# Sheet1.net
KiCad netlist of a schematic drawn in Altium Designer
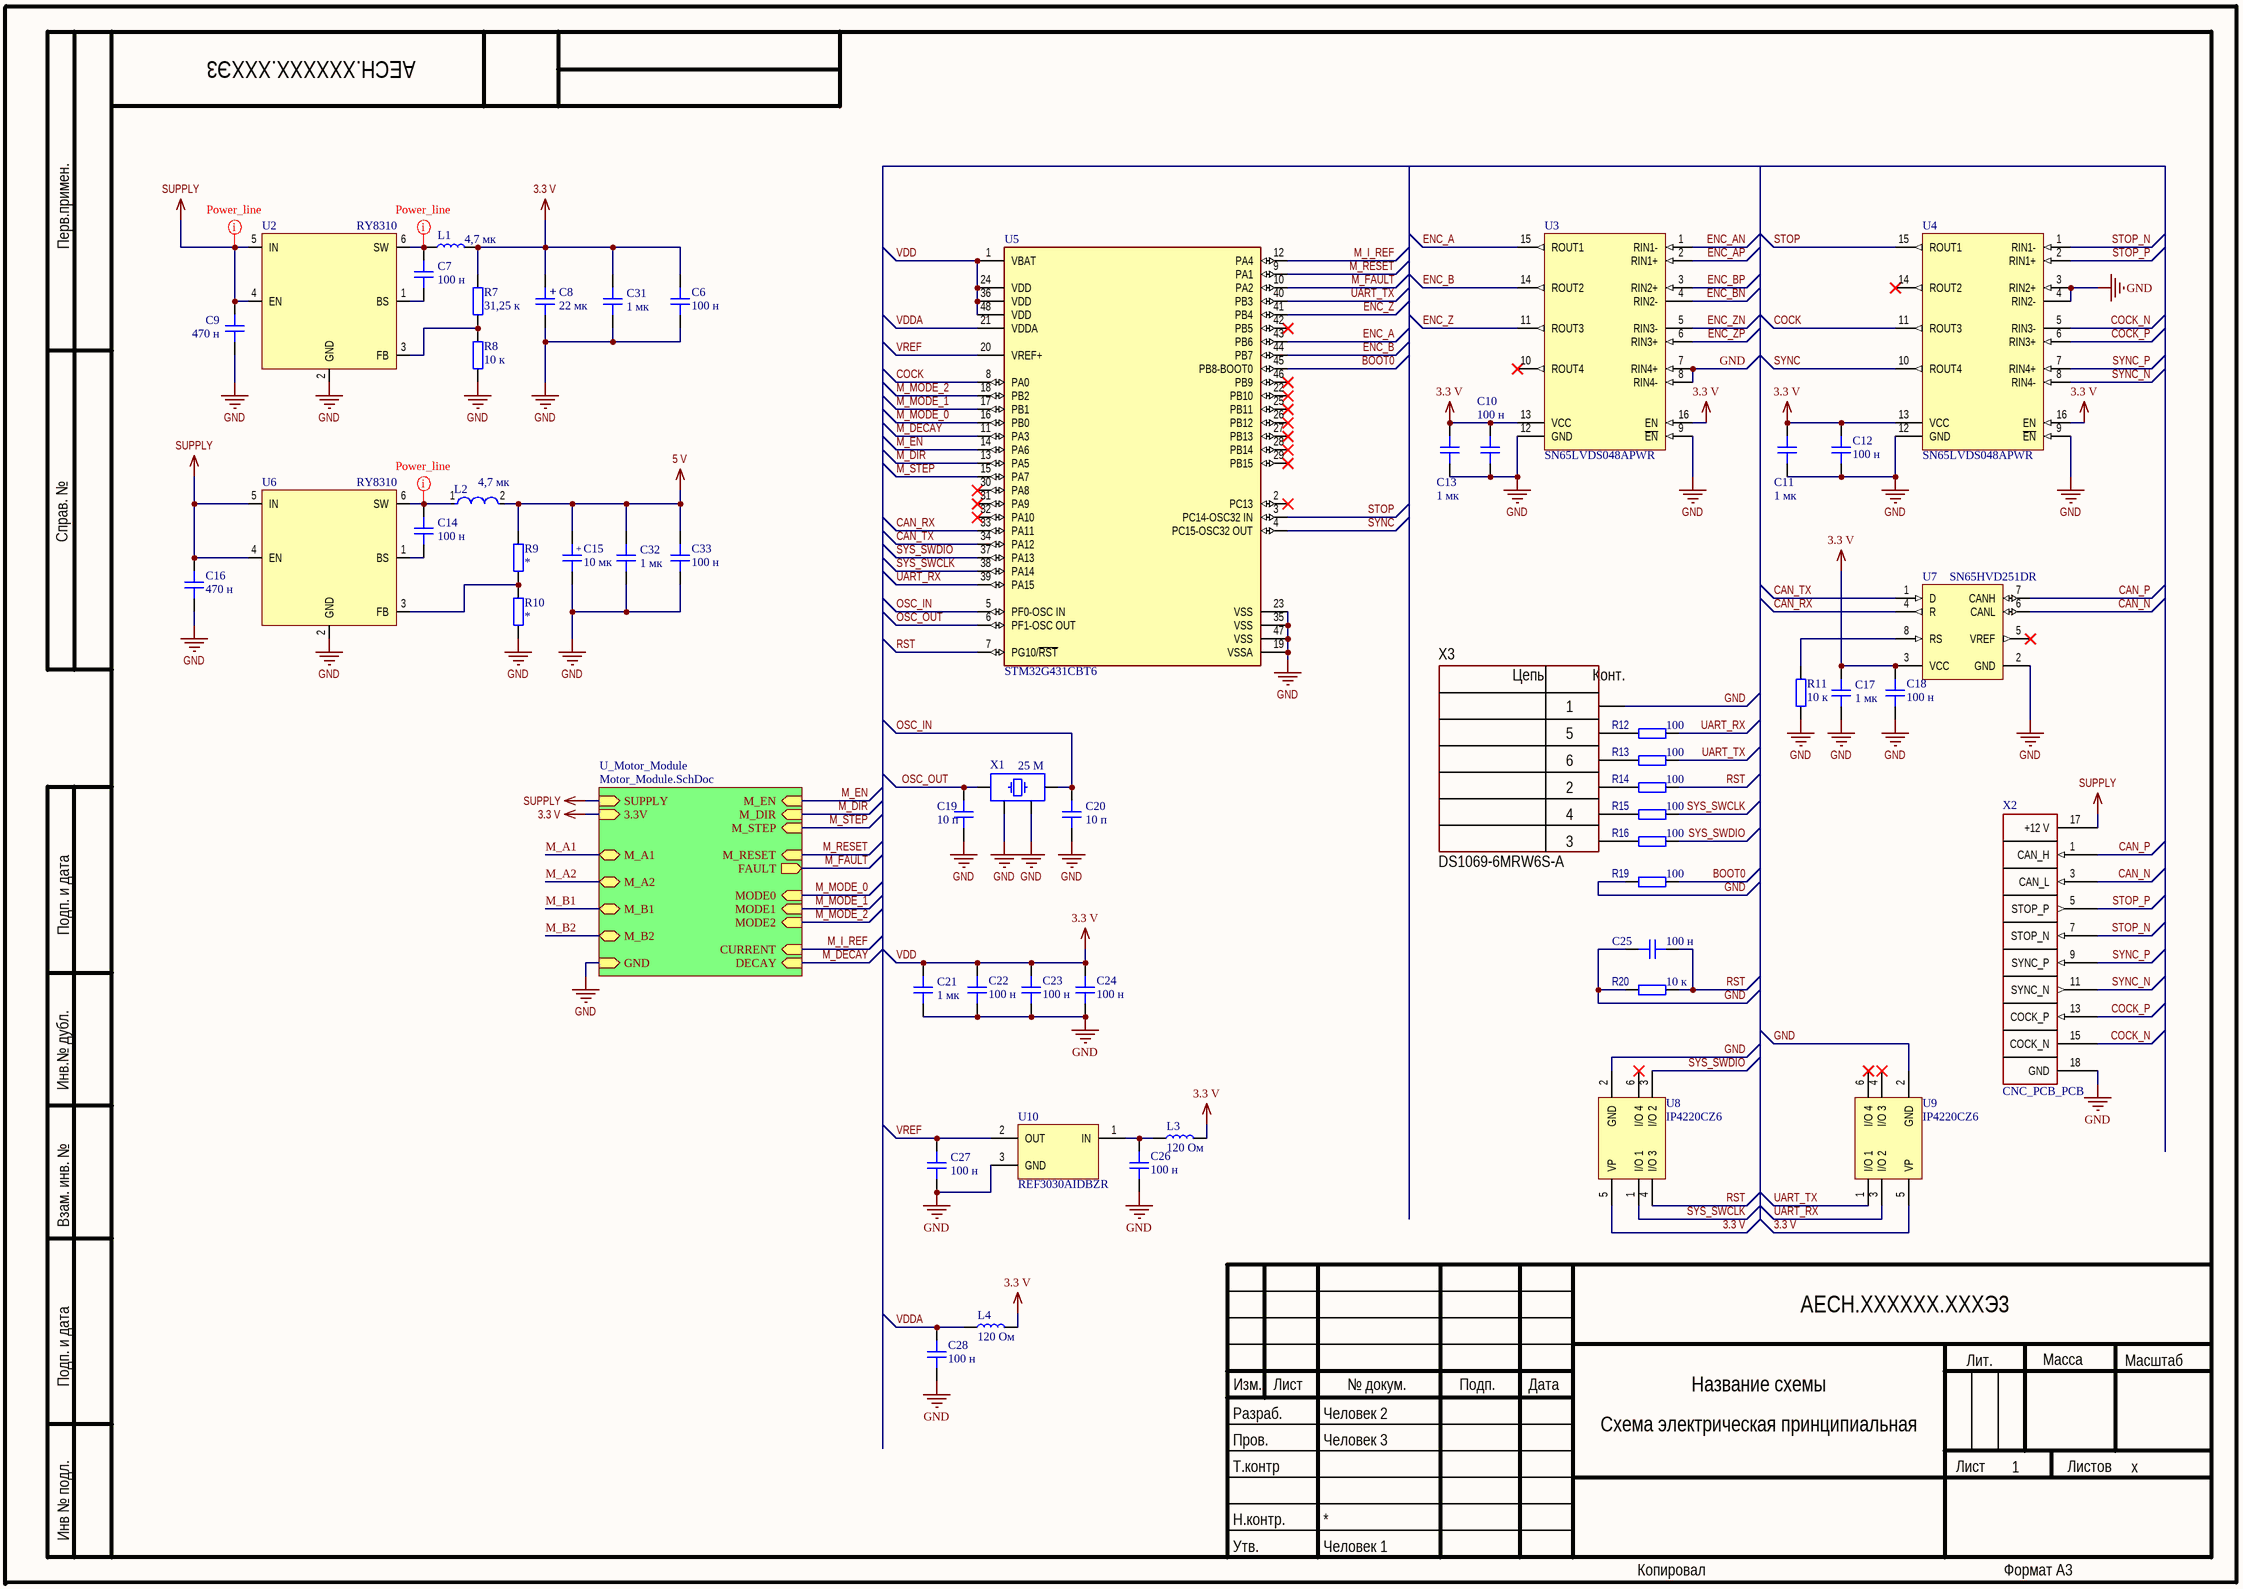
[diagram p0: Sheet1.SchDoc]

(export (version "E")
  (design (tool "Eeschema 10.0.6"))
  (components
    (comp (ref "C6")
      (value "100 н")
      (footprint "CAP_0603")
      (description "Керамический конденсатор")
      (libsource (lib "Schematic-Lib-PhilsLab") (part "CAP_0603"))
    )
    (comp (ref "C7")
      (value "100 н")
      (footprint "CAP_0603")
      (description "Керамический конденсатор")
      (libsource (lib "Schematic-Lib-PhilsLab") (part "CAP_0805"))
    )
    (comp (ref "C8")
      (value "22 мк")
      (footprint "TANTAL_B")
      (description "Танталовый конденсатор")
      (fields (field (name "VOLTAGE") "6,3"))
      (libsource (lib "Schematic-Lib-PhilsLab") (part "CAP_ALEL_16x16.5_25V"))
    )
    (comp (ref "C9")
      (value "470 н")
      (footprint "CAP_0805")
      (description "Capacitor SMD 0805")
      (fields (field (name "VOLTAGE") "50"))
      (libsource (lib "Schematic-Lib-PhilsLab") (part "CAP_0805"))
    )
    (comp (ref "C10")
      (value "100 н")
      (footprint "CAP_0603")
      (description "Керамический конденсатор")
      (libsource (lib "Schematic-Lib-PhilsLab") (part "CAP_0603"))
    )
    (comp (ref "C11")
      (value "1 мк")
      (footprint "CAP_0603")
      (description "Керамический конденсатор")
      (libsource (lib "Schematic-Lib-PhilsLab") (part "CAP_0603"))
    )
    (comp (ref "C12")
      (value "100 н")
      (footprint "CAP_0603")
      (description "Керамический конденсатор")
      (libsource (lib "Schematic-Lib-PhilsLab") (part "CAP_0603"))
    )
    (comp (ref "C13")
      (value "1 мк")
      (footprint "CAP_0603")
      (description "Керамический конденсатор")
      (libsource (lib "Schematic-Lib-PhilsLab") (part "CAP_0603"))
    )
    (comp (ref "C14")
      (value "100 н")
      (footprint "CAP_0603")
      (description "Керамический конденсатор")
      (libsource (lib "Schematic-Lib-PhilsLab") (part "CAP_0805"))
    )
    (comp (ref "C15")
      (value "10 мк")
      (footprint "CAP_TANT_0603")
      (description "Capacitor SMD Tantalum 0603")
      (fields (field (name "VOLTAGE") "6,3"))
      (libsource (lib "Schematic-Lib-PhilsLab") (part "CAP_TANT_0603"))
    )
    (comp (ref "C16")
      (value "470 н")
      (footprint "CAP_0805")
      (description "Capacitor SMD 0805")
      (fields (field (name "VOLTAGE") "50"))
      (libsource (lib "Schematic-Lib-PhilsLab") (part "CAP_0805"))
    )
    (comp (ref "C17")
      (value "1 мк")
      (footprint "CAP_0603")
      (description "Керамический конденсатор")
      (libsource (lib "Schematic-Lib-PhilsLab") (part "CAP_0603"))
    )
    (comp (ref "C18")
      (value "100 н")
      (footprint "CAP_0603")
      (description "Керамический конденсатор")
      (libsource (lib "Schematic-Lib-PhilsLab") (part "CAP_0603"))
    )
    (comp (ref "C19")
      (value "10 п")
      (footprint "CAP_0603")
      (description "Керамический конденсатор")
      (libsource (lib "Schematic-Lib-PhilsLab") (part "CAP_0603"))
    )
    (comp (ref "C20")
      (value "10 п")
      (footprint "CAP_0603")
      (description "Керамический конденсатор")
      (libsource (lib "Schematic-Lib-PhilsLab") (part "CAP_0603"))
    )
    (comp (ref "C21")
      (value "1 мк")
      (footprint "CAP_0603")
      (description "Керамический конденсатор")
      (libsource (lib "Schematic-Lib-PhilsLab") (part "CAP_0603"))
    )
    (comp (ref "C22")
      (value "100 н")
      (footprint "CAP_0603")
      (description "Керамический конденсатор")
      (libsource (lib "Schematic-Lib-PhilsLab") (part "CAP_0603"))
    )
    (comp (ref "C23")
      (value "100 н")
      (footprint "CAP_0603")
      (description "Керамический конденсатор")
      (libsource (lib "Schematic-Lib-PhilsLab") (part "CAP_0603"))
    )
    (comp (ref "C24")
      (value "100 н")
      (footprint "CAP_0603")
      (description "Керамический конденсатор")
      (libsource (lib "Schematic-Lib-PhilsLab") (part "CAP_0603"))
    )
    (comp (ref "C25")
      (value "100 н")
      (footprint "CAP_0603")
      (description "Керамический конденсатор")
      (libsource (lib "Schematic-Lib-PhilsLab") (part "CAP_0603"))
    )
    (comp (ref "C26")
      (value "100 н")
      (footprint "CAP_0603")
      (description "Capacitor SMD 0603")
      (libsource (lib "Schematic-Lib-PhilsLab") (part "CAP_0603"))
    )
    (comp (ref "C27")
      (value "100 н")
      (footprint "CAP_0603")
      (description "Керамический конденсатор")
      (libsource (lib "Schematic-Lib-PhilsLab") (part "CAP_0603"))
    )
    (comp (ref "C28")
      (value "100 н")
      (footprint "CAP_0603")
      (description "Capacitor SMD 0603")
      (libsource (lib "Schematic-Lib-PhilsLab") (part "CAP_0603"))
    )
    (comp (ref "C31")
      (value "1 мк")
      (footprint "CAP_0603")
      (description "Керамический конденсатор")
      (libsource (lib "Schematic-Lib-PhilsLab") (part "CAP_0603"))
    )
    (comp (ref "C32")
      (value "1 мк")
      (footprint "CAP_0603")
      (description "Керамический конденсатор")
      (libsource (lib "Schematic-Lib-PhilsLab") (part "CAP_0603"))
    )
    (comp (ref "C33")
      (value "100 н")
      (footprint "CAP_0603")
      (description "Керамический конденсатор")
      (libsource (lib "Schematic-Lib-PhilsLab") (part "CAP_0603"))
    )
    (comp (ref "L1")
      (value "4,7 мк")
      (footprint "IND_1008")
      (description "Inductor SMD 1008")
      (libsource (lib "Schematic-Lib-PhilsLab") (part "IND_1008"))
    )
    (comp (ref "L2")
      (value "4,7 мк")
      (footprint "FP-LQM21PH_G0-IPC_C")
      (description "Multilayer Type Inductor for Power Lines, 0805 (2012), 4.7μH, 20%, 0.288Ω, 0.8A")
      (libsource (lib "Altium Content Vault") (part "725321dda6339637d4d059423bc1c3c"))
    )
    (comp (ref "L3")
      (value "120 Ом")
      (footprint "IND_0603")
      (description "Inductor SMD 0603")
      (libsource (lib "Schematic-Lib-PhilsLab") (part "IND_0603"))
    )
    (comp (ref "L4")
      (value "120 Ом")
      (footprint "IND_0603")
      (description "Inductor SMD 0603")
      (libsource (lib "Schematic-Lib-PhilsLab") (part "IND_0603"))
    )
    (comp (ref "R7")
      (value "31,25 к")
      (footprint "RES_0603")
      (description "Резистор")
      (libsource (lib "Schematic-Lib-PhilsLab") (part "RES_0805"))
    )
    (comp (ref "R8")
      (value "10 к")
      (footprint "RES_0603")
      (description "Резистор")
      (libsource (lib "Schematic-Lib-PhilsLab") (part "RES_0805"))
    )
    (comp (ref "R9")
      (value "*")
      (footprint "RES_0603")
      (description "Резистор")
      (libsource (lib "Schematic-Lib-PhilsLab") (part "RES_0805"))
    )
    (comp (ref "R10")
      (value "*")
      (footprint "RES_0603")
      (description "Резистор")
      (libsource (lib "Schematic-Lib-PhilsLab") (part "RES_0805"))
    )
    (comp (ref "R11")
      (value "10 к")
      (footprint "RES_0603")
      (description "Резистор")
      (libsource (lib "Schematic-Lib-PhilsLab") (part "RES_0603"))
    )
    (comp (ref "R12")
      (value "100")
      (footprint "RES_0603")
      (description "Резистор")
      (libsource (lib "Schematic-Lib-PhilsLab") (part "RES_0603"))
    )
    (comp (ref "R13")
      (value "100")
      (footprint "RES_0603")
      (description "Резистор")
      (libsource (lib "Schematic-Lib-PhilsLab") (part "RES_0603"))
    )
    (comp (ref "R14")
      (value "100")
      (footprint "RES_0603")
      (description "Резистор")
      (libsource (lib "Schematic-Lib-PhilsLab") (part "RES_0603"))
    )
    (comp (ref "R15")
      (value "100")
      (footprint "RES_0603")
      (description "Резистор")
      (libsource (lib "Schematic-Lib-PhilsLab") (part "RES_0603"))
    )
    (comp (ref "R16")
      (value "100")
      (footprint "RES_0603")
      (description "Резистор")
      (libsource (lib "Schematic-Lib-PhilsLab") (part "RES_0603"))
    )
    (comp (ref "R19")
      (value "100")
      (footprint "RES_0603")
      (description "Резистор")
      (libsource (lib "Schematic-Lib-PhilsLab") (part "RES_0603"))
    )
    (comp (ref "R20")
      (value "10 к")
      (footprint "RES_0603")
      (description "Резистор")
      (libsource (lib "Schematic-Lib-PhilsLab") (part "RES_0603"))
    )
    (comp (ref "U2")
      (value "RY8310")
      (footprint "SOT-23-6")
      (description "Понижающий DC-DC")
      (libsource (lib "Schematic-Lib-PhilsLab") (part "MT2492"))
    )
    (comp (ref "U3")
      (value "SN65LVDS048APWR")
      (footprint "MTC16_M")
      (description "Драйвер LVDS")
      (libsource (lib "Altium Content Vault") (part "IN-LNDRV-DS90LV047ATM"))
    )
    (comp (ref "U4")
      (value "SN65LVDS048APWR")
      (footprint "MTC16_M")
      (description "Драйвер LVDS")
      (libsource (lib "Altium Content Vault") (part "IN-LNDRV-DS90LV047ATM"))
    )
    (comp (ref "U5")
      (value "STM32G431CBT6")
      (footprint "FP-LQFP48-5B-MFG")
      (description "MAINSTREAM ARM CORTEX-M4+ MCU 17")
      (libsource (lib "Altium Content Vault") (part "08b09c1d51ec08ade740842f2b8671b"))
    )
    (comp (ref "U6")
      (value "RY8310")
      (footprint "SOT-23-6")
      (description "Понижающий DC-DC")
      (libsource (lib "Schematic-Lib-PhilsLab") (part "MT2492"))
    )
    (comp (ref "U7")
      (value "SN65HVD251DR")
      (footprint "D0008A_N")
      (description "Драйвер CAN")
      (libsource (lib "Altium Content Vault") (part "TI-SN65HVD251-SOIC_D-8"))
    )
    (comp (ref "U8")
      (value "IP4220CZ6")
      (footprint "NXP-SOT457_L")
      (description "Сборка защитных диодов")
      (libsource (lib "") (part "NXP-IP4220CZ6-6_1"))
    )
    (comp (ref "U9")
      (value "IP4220CZ6")
      (footprint "NXP-SOT457_L")
      (description "Сборка защитных диодов")
      (libsource (lib "Altium Content Vault") (part "NXP-IP4220CZ6-6"))
    )
    (comp (ref "U10")
      (value "REF3030AIDBZR")
      (footprint "DBZ0003A_N")
      (libsource (lib "Altium Content Vault") (part "TI-REF3020DBZ3"))
    )
    (comp (ref "X1")
      (value "25 M")
      (footprint "XTAL_3225")
      (description "Кварцевый резонатор")
      (libsource (lib "Schematic-Lib-PhilsLab") (part "TSX-3225_24.0000MF15X-AC"))
    )
    (comp (ref "X2")
      (value "CNC_PCB_PCB")
      (footprint "CNC_PCB_PCB")
      (libsource (lib "BarkockLib") (part "CNC_PCB_PCB"))
    )
    (comp (ref "X3")
      (value "DS1069-6MRW6S-A")
      (footprint "CON: CWF-6R")
      (libsource (lib "Connectors") (part "6-Connector"))
    )
  )
  (nets
    (net (code "1") (name "/BOOT0") (class "Default")
      (node (ref "R19") (pin "1") (pinfunction "1_1") (pintype "passive"))
      (node (ref "U5") (pin "45") (pinfunction "PB8-BOOT0_45") (pintype "bidirectional"))
    )
    (net (code "2") (name "/CAN_N") (class "Default")
      (node (ref "U7") (pin "6") (pinfunction "CANL_6") (pintype "bidirectional"))
      (node (ref "X2") (pin "3") (pinfunction "CAN_L_3") (pintype "input"))
    )
    (net (code "3") (name "/CAN_P") (class "Default")
      (node (ref "U7") (pin "7") (pinfunction "CANH_7") (pintype "bidirectional"))
      (node (ref "X2") (pin "1") (pinfunction "CAN_H_1") (pintype "input"))
    )
    (net (code "4") (name "/CAN_RX") (class "Default")
      (node (ref "U5") (pin "33") (pinfunction "PA11_33") (pintype "bidirectional"))
      (node (ref "U7") (pin "4") (pinfunction "R_4") (pintype "output"))
    )
    (net (code "5") (name "/CAN_TX") (class "Default")
      (node (ref "U5") (pin "34") (pinfunction "PA12_34") (pintype "bidirectional"))
      (node (ref "U7") (pin "1") (pinfunction "D_1") (pintype "input"))
    )
    (net (code "6") (name "/COCK") (class "Default")
      (node (ref "U4") (pin "11") (pinfunction "ROUT3_11") (pintype "output"))
      (node (ref "U5") (pin "8") (pinfunction "PA0_8") (pintype "bidirectional"))
    )
    (net (code "7") (name "/COCK_N") (class "Default")
      (node (ref "U4") (pin "5") (pinfunction "RIN3-_5") (pintype "power_in"))
      (node (ref "X2") (pin "15") (pinfunction "COCK_N_15") (pintype "power_in"))
    )
    (net (code "8") (name "/COCK_P") (class "Default")
      (node (ref "U4") (pin "6") (pinfunction "RIN3+_6") (pintype "input"))
      (node (ref "X2") (pin "13") (pinfunction "COCK_P_13") (pintype "input"))
    )
    (net (code "9") (name "/ENC_A") (class "Default")
      (node (ref "U3") (pin "15") (pinfunction "ROUT1_15") (pintype "output"))
      (node (ref "U5") (pin "43") (pinfunction "PB6_43") (pintype "bidirectional"))
    )
    (net (code "10") (name "/ENC_AN") (class "Default")
      (node (ref "U3") (pin "1") (pinfunction "RIN1-_1") (pintype "input"))
    )
    (net (code "11") (name "/ENC_AP") (class "Default")
      (node (ref "U3") (pin "2") (pinfunction "RIN1+_2") (pintype "input"))
    )
    (net (code "12") (name "/ENC_B") (class "Default")
      (node (ref "U3") (pin "14") (pinfunction "ROUT2_14") (pintype "output"))
      (node (ref "U5") (pin "44") (pinfunction "PB7_44") (pintype "bidirectional"))
    )
    (net (code "13") (name "/ENC_BN") (class "Default")
      (node (ref "U3") (pin "4") (pinfunction "RIN2-_4") (pintype "power_in"))
    )
    (net (code "14") (name "/ENC_BP") (class "Default")
      (node (ref "U3") (pin "3") (pinfunction "RIN2+_3") (pintype "input"))
    )
    (net (code "15") (name "/ENC_Z") (class "Default")
      (node (ref "U3") (pin "11") (pinfunction "ROUT3_11") (pintype "output"))
      (node (ref "U5") (pin "41") (pinfunction "PB4_41") (pintype "bidirectional"))
    )
    (net (code "16") (name "/ENC_ZN") (class "Default")
      (node (ref "U3") (pin "5") (pinfunction "RIN3-_5") (pintype "power_in"))
    )
    (net (code "17") (name "/ENC_ZP") (class "Default")
      (node (ref "U3") (pin "6") (pinfunction "RIN3+_6") (pintype "input"))
    )
    (net (code "22") (name "/M_DECAY") (class "Default")
      (node (ref "U5") (pin "11") (pinfunction "PA3_11") (pintype "bidirectional"))
    )
    (net (code "23") (name "/M_DIR") (class "Default")
      (node (ref "U5") (pin "13") (pinfunction "PA5_13") (pintype "bidirectional"))
    )
    (net (code "24") (name "/M_EN") (class "Default")
      (node (ref "U5") (pin "14") (pinfunction "PA6_14") (pintype "bidirectional"))
    )
    (net (code "25") (name "/M_FAULT") (class "Default")
      (node (ref "U5") (pin "10") (pinfunction "PA2_10") (pintype "bidirectional"))
    )
    (net (code "26") (name "/M_I_REF") (class "Default")
      (node (ref "U5") (pin "12") (pinfunction "PA4_12") (pintype "bidirectional"))
    )
    (net (code "27") (name "/M_MODE_0") (class "Default")
      (node (ref "U5") (pin "16") (pinfunction "PB0_16") (pintype "bidirectional"))
    )
    (net (code "28") (name "/M_MODE_1") (class "Default")
      (node (ref "U5") (pin "17") (pinfunction "PB1_17") (pintype "bidirectional"))
    )
    (net (code "29") (name "/M_MODE_2") (class "Default")
      (node (ref "U5") (pin "18") (pinfunction "PB2_18") (pintype "bidirectional"))
    )
    (net (code "30") (name "/M_RESET") (class "Default")
      (node (ref "U5") (pin "9") (pinfunction "PA1_9") (pintype "bidirectional"))
    )
    (net (code "31") (name "/M_STEP") (class "Default")
      (node (ref "U5") (pin "15") (pinfunction "PA7_15") (pintype "bidirectional"))
    )
    (net (code "32") (name "/OSC_IN") (class "Default")
      (node (ref "C20") (pin "1") (pinfunction "1_1") (pintype "passive"))
      (node (ref "U5") (pin "5") (pinfunction "PF0-OSC_IN_5") (pintype "bidirectional"))
      (node (ref "X1") (pin "3") (pinfunction "3_3") (pintype "passive"))
    )
    (net (code "33") (name "/OSC_OUT") (class "Default")
      (node (ref "C19") (pin "1") (pinfunction "1_1") (pintype "passive"))
      (node (ref "U5") (pin "6") (pinfunction "PF1-OSC_OUT_6") (pintype "bidirectional"))
      (node (ref "X1") (pin "1") (pinfunction "1_1") (pintype "passive"))
    )
    (net (code "34") (name "/RST") (class "Default")
      (node (ref "C25") (pin "2") (pinfunction "2_2") (pintype "passive"))
      (node (ref "R14") (pin "1") (pinfunction "1_1") (pintype "passive"))
      (node (ref "R20") (pin "1") (pinfunction "1_1") (pintype "passive"))
      (node (ref "U5") (pin "7") (pinfunction "PG10/~{RST}_7") (pintype "bidirectional"))
      (node (ref "U8") (pin "4") (pinfunction "I/O_3_4") (pintype "passive"))
    )
    (net (code "35") (name "/STOP") (class "Default")
      (node (ref "U4") (pin "15") (pinfunction "ROUT1_15") (pintype "output"))
      (node (ref "U5") (pin "3") (pinfunction "PC14-OSC32_IN_3") (pintype "bidirectional"))
    )
    (net (code "36") (name "/STOP_N") (class "Default")
      (node (ref "U4") (pin "1") (pinfunction "RIN1-_1") (pintype "input"))
      (node (ref "X2") (pin "7") (pinfunction "STOP_N_7") (pintype "input"))
    )
    (net (code "37") (name "/STOP_P") (class "Default")
      (node (ref "U4") (pin "2") (pinfunction "RIN1+_2") (pintype "input"))
      (node (ref "X2") (pin "5") (pinfunction "STOP_P_5") (pintype "output"))
    )
    (net (code "38") (name "/SYNC") (class "Default")
      (node (ref "U4") (pin "10") (pinfunction "ROUT4_10") (pintype "output"))
      (node (ref "U5") (pin "4") (pinfunction "PC15-OSC32_OUT_4") (pintype "bidirectional"))
    )
    (net (code "39") (name "/SYNC_N") (class "Default")
      (node (ref "U4") (pin "8") (pinfunction "RIN4-_8") (pintype "input"))
      (node (ref "X2") (pin "11") (pinfunction "SYNC_N_11") (pintype "output"))
    )
    (net (code "40") (name "/SYNC_P") (class "Default")
      (node (ref "U4") (pin "7") (pinfunction "RIN4+_7") (pintype "input"))
      (node (ref "X2") (pin "9") (pinfunction "SYNC_P_9") (pintype "input"))
    )
    (net (code "41") (name "/SYS_SWCLK") (class "Default")
      (node (ref "R15") (pin "1") (pinfunction "1_1") (pintype "passive"))
      (node (ref "U5") (pin "38") (pinfunction "PA14_38") (pintype "bidirectional"))
      (node (ref "U8") (pin "1") (pinfunction "I/O_1_1") (pintype "passive"))
    )
    (net (code "42") (name "/SYS_SWDIO") (class "Default")
      (node (ref "R16") (pin "1") (pinfunction "1_1") (pintype "passive"))
      (node (ref "U5") (pin "37") (pinfunction "PA13_37") (pintype "bidirectional"))
      (node (ref "U8") (pin "3") (pinfunction "I/O_2_3") (pintype "passive"))
    )
    (net (code "43") (name "/UART_RX") (class "Default")
      (node (ref "R12") (pin "1") (pinfunction "1_1") (pintype "passive"))
      (node (ref "U5") (pin "39") (pinfunction "PA15_39") (pintype "bidirectional"))
      (node (ref "U9") (pin "3") (pinfunction "I/O_2_3") (pintype "passive"))
    )
    (net (code "44") (name "/UART_TX") (class "Default")
      (node (ref "R13") (pin "1") (pinfunction "1_1") (pintype "passive"))
      (node (ref "U5") (pin "40") (pinfunction "PB3_40") (pintype "bidirectional"))
      (node (ref "U9") (pin "1") (pinfunction "I/O_1_1") (pintype "passive"))
    )
    (net (code "45") (name "/VDDA") (class "Default")
      (node (ref "C28") (pin "1") (pinfunction "1_1") (pintype "passive"))
      (node (ref "L4") (pin "1") (pinfunction "1_1") (pintype "passive"))
      (node (ref "U5") (pin "21") (pinfunction "VDDA_21") (pintype "power_in"))
    )
    (net (code "46") (name "/VREF") (class "Default")
      (node (ref "C27") (pin "2") (pinfunction "2_2") (pintype "passive"))
      (node (ref "U10") (pin "2") (pinfunction "OUT_2") (pintype "power_in"))
      (node (ref "U5") (pin "20") (pinfunction "VREF+_20") (pintype "power_in"))
    )
    (net (code "47") (name "3.3 V") (class "Default")
      (node (ref "C10") (pin "2") (pinfunction "2_2") (pintype "passive"))
      (node (ref "C11") (pin "2") (pinfunction "2_2") (pintype "passive"))
      (node (ref "C12") (pin "2") (pinfunction "2_2") (pintype "passive"))
      (node (ref "C13") (pin "2") (pinfunction "2_2") (pintype "passive"))
      (node (ref "C17") (pin "2") (pinfunction "2_2") (pintype "passive"))
      (node (ref "C18") (pin "1") (pinfunction "1_1") (pintype "passive"))
      (node (ref "C21") (pin "2") (pinfunction "2_2") (pintype "passive"))
      (node (ref "C22") (pin "1") (pinfunction "1_1") (pintype "passive"))
      (node (ref "C23") (pin "1") (pinfunction "1_1") (pintype "passive"))
      (node (ref "C24") (pin "1") (pinfunction "1_1") (pintype "passive"))
      (node (ref "C31") (pin "2") (pinfunction "2_2") (pintype "passive"))
      (node (ref "C6") (pin "1") (pinfunction "1_1") (pintype "passive"))
      (node (ref "C8") (pin "1") (pinfunction "1_1") (pintype "passive"))
      (node (ref "L1") (pin "2") (pinfunction "2_2") (pintype "passive"))
      (node (ref "L3") (pin "2") (pinfunction "2_2") (pintype "passive"))
      (node (ref "L4") (pin "2") (pinfunction "2_2") (pintype "passive"))
      (node (ref "R7") (pin "1") (pinfunction "1_1") (pintype "passive"))
      (node (ref "U3") (pin "13") (pinfunction "VCC_13") (pintype "power_in"))
      (node (ref "U3") (pin "16") (pinfunction "EN_16") (pintype "input"))
      (node (ref "U4") (pin "13") (pinfunction "VCC_13") (pintype "power_in"))
      (node (ref "U4") (pin "16") (pinfunction "EN_16") (pintype "input"))
      (node (ref "U5") (pin "1") (pinfunction "VBAT_1") (pintype "power_in"))
      (node (ref "U5") (pin "24") (pinfunction "VDD_24") (pintype "power_in"))
      (node (ref "U5") (pin "36") (pinfunction "VDD_36") (pintype "power_in"))
      (node (ref "U5") (pin "48") (pinfunction "VDD_48") (pintype "power_in"))
      (node (ref "U7") (pin "3") (pinfunction "VCC_3") (pintype "power_in"))
      (node (ref "U8") (pin "5") (pinfunction "VP_5") (pintype "power_in"))
      (node (ref "U9") (pin "5") (pinfunction "VP_5") (pintype "power_in"))
    )
    (net (code "48") (name "5 V") (class "Default")
      (node (ref "C15") (pin "A") (pinfunction "A_A") (pintype "passive"))
      (node (ref "C32") (pin "2") (pinfunction "2_2") (pintype "passive"))
      (node (ref "C33") (pin "1") (pinfunction "1_1") (pintype "passive"))
      (node (ref "L2") (pin "2") (pinfunction "2_2") (pintype "passive"))
      (node (ref "R9") (pin "1") (pinfunction "1_1") (pintype "passive"))
    )
    (net (code "49") (name "GND") (class "Default")
      (node (ref "C10") (pin "1") (pinfunction "1_1") (pintype "passive"))
      (node (ref "C11") (pin "1") (pinfunction "1_1") (pintype "passive"))
      (node (ref "C12") (pin "1") (pinfunction "1_1") (pintype "passive"))
      (node (ref "C13") (pin "1") (pinfunction "1_1") (pintype "passive"))
      (node (ref "C15") (pin "K") (pinfunction "K_K") (pintype "passive"))
      (node (ref "C16") (pin "2") (pinfunction "2_2") (pintype "passive"))
      (node (ref "C17") (pin "1") (pinfunction "1_1") (pintype "passive"))
      (node (ref "C18") (pin "2") (pinfunction "2_2") (pintype "passive"))
      (node (ref "C19") (pin "2") (pinfunction "2_2") (pintype "passive"))
      (node (ref "C20") (pin "2") (pinfunction "2_2") (pintype "passive"))
      (node (ref "C21") (pin "1") (pinfunction "1_1") (pintype "passive"))
      (node (ref "C22") (pin "2") (pinfunction "2_2") (pintype "passive"))
      (node (ref "C23") (pin "2") (pinfunction "2_2") (pintype "passive"))
      (node (ref "C24") (pin "2") (pinfunction "2_2") (pintype "passive"))
      (node (ref "C25") (pin "1") (pinfunction "1_1") (pintype "passive"))
      (node (ref "C26") (pin "2") (pinfunction "2_2") (pintype "passive"))
      (node (ref "C27") (pin "1") (pinfunction "1_1") (pintype "passive"))
      (node (ref "C28") (pin "2") (pinfunction "2_2") (pintype "passive"))
      (node (ref "C31") (pin "1") (pinfunction "1_1") (pintype "passive"))
      (node (ref "C32") (pin "1") (pinfunction "1_1") (pintype "passive"))
      (node (ref "C33") (pin "2") (pinfunction "2_2") (pintype "passive"))
      (node (ref "C6") (pin "2") (pinfunction "2_2") (pintype "passive"))
      (node (ref "C8") (pin "2") (pinfunction "2_2") (pintype "passive"))
      (node (ref "C9") (pin "2") (pinfunction "2_2") (pintype "passive"))
      (node (ref "R10") (pin "2") (pinfunction "2_2") (pintype "passive"))
      (node (ref "R11") (pin "1") (pinfunction "1_1") (pintype "passive"))
      (node (ref "R19") (pin "2") (pinfunction "2_2") (pintype "passive"))
      (node (ref "R20") (pin "2") (pinfunction "2_2") (pintype "passive"))
      (node (ref "R8") (pin "2") (pinfunction "2_2") (pintype "passive"))
      (node (ref "U10") (pin "3") (pinfunction "GND_3") (pintype "power_in"))
      (node (ref "U2") (pin "2") (pinfunction "GND_2") (pintype "passive"))
      (node (ref "U3") (pin "12") (pinfunction "GND_12") (pintype "power_in"))
      (node (ref "U3") (pin "7") (pinfunction "RIN4+_7") (pintype "input"))
      (node (ref "U3") (pin "8") (pinfunction "RIN4-_8") (pintype "input"))
      (node (ref "U3") (pin "9") (pinfunction "~{EN}_9") (pintype "input"))
      (node (ref "U4") (pin "12") (pinfunction "GND_12") (pintype "power_in"))
      (node (ref "U4") (pin "3") (pinfunction "RIN2+_3") (pintype "input"))
      (node (ref "U4") (pin "4") (pinfunction "RIN2-_4") (pintype "power_in"))
      (node (ref "U4") (pin "9") (pinfunction "~{EN}_9") (pintype "input"))
      (node (ref "U5") (pin "19") (pinfunction "VSSA_19") (pintype "power_in"))
      (node (ref "U5") (pin "23") (pinfunction "VSS_23") (pintype "power_in"))
      (node (ref "U5") (pin "35") (pinfunction "VSS_35") (pintype "power_in"))
      (node (ref "U5") (pin "47") (pinfunction "VSS_47") (pintype "power_in"))
      (node (ref "U6") (pin "2") (pinfunction "GND_2") (pintype "passive"))
      (node (ref "U7") (pin "2") (pinfunction "GND_2") (pintype "power_in"))
      (node (ref "U8") (pin "2") (pinfunction "GND_2") (pintype "power_in"))
      (node (ref "U9") (pin "2") (pinfunction "GND_2") (pintype "power_in"))
      (node (ref "X1") (pin "2") (pinfunction "2_2") (pintype "passive"))
      (node (ref "X1") (pin "4") (pinfunction "4_4") (pintype "passive"))
      (node (ref "X2") (pin "18") (pinfunction "GND_18") (pintype "power_in"))
      (node (ref "X3") (pin "1") (pinfunction "1_1") (pintype "passive"))
    )
    (net (code "50") (name "Net-(R12-Pad2)") (class "Default")
      (node (ref "R12") (pin "2") (pinfunction "2_2") (pintype "passive"))
      (node (ref "X3") (pin "5") (pinfunction "5_5") (pintype "passive"))
    )
    (net (code "51") (name "Net-(R13-Pad2)") (class "Default")
      (node (ref "R13") (pin "2") (pinfunction "2_2") (pintype "passive"))
      (node (ref "X3") (pin "6") (pinfunction "6_6") (pintype "power_in"))
    )
    (net (code "52") (name "Net-(R14-Pad2)") (class "Default")
      (node (ref "R14") (pin "2") (pinfunction "2_2") (pintype "passive"))
      (node (ref "X3") (pin "2") (pinfunction "2_2") (pintype "power_in"))
    )
    (net (code "53") (name "Net-(R15-Pad2)") (class "Default")
      (node (ref "R15") (pin "2") (pinfunction "2_2") (pintype "passive"))
      (node (ref "X3") (pin "4") (pinfunction "4_4") (pintype "power_in"))
    )
    (net (code "54") (name "Net-(R16-Pad2)") (class "Default")
      (node (ref "R16") (pin "2") (pinfunction "2_2") (pintype "passive"))
      (node (ref "X3") (pin "3") (pinfunction "3_3") (pintype "power_in"))
    )
    (net (code "55") (name "Net-(U2-BS)") (class "Default")
      (node (ref "C7") (pin "1") (pinfunction "1_1") (pintype "passive"))
      (node (ref "U2") (pin "1") (pinfunction "BS_1") (pintype "passive"))
    )
    (net (code "56") (name "Net-(U2-FB)") (class "Default")
      (node (ref "R7") (pin "2") (pinfunction "2_2") (pintype "passive"))
      (node (ref "R8") (pin "1") (pinfunction "1_1") (pintype "passive"))
      (node (ref "U2") (pin "3") (pinfunction "FB_3") (pintype "passive"))
    )
    (net (code "57") (name "Net-(U2-SW)") (class "Default")
      (node (ref "C7") (pin "2") (pinfunction "2_2") (pintype "passive"))
      (node (ref "L1") (pin "1") (pinfunction "1_1") (pintype "passive"))
      (node (ref "U2") (pin "6") (pinfunction "SW_6") (pintype "passive"))
    )
    (net (code "58") (name "Net-(U6-BS)") (class "Default")
      (node (ref "C14") (pin "1") (pinfunction "1_1") (pintype "passive"))
      (node (ref "U6") (pin "1") (pinfunction "BS_1") (pintype "passive"))
    )
    (net (code "59") (name "Net-(U6-FB)") (class "Default")
      (node (ref "R10") (pin "1") (pinfunction "1_1") (pintype "passive"))
      (node (ref "R9") (pin "2") (pinfunction "2_2") (pintype "passive"))
      (node (ref "U6") (pin "3") (pinfunction "FB_3") (pintype "passive"))
    )
    (net (code "60") (name "Net-(U6-SW)") (class "Default")
      (node (ref "C14") (pin "2") (pinfunction "2_2") (pintype "passive"))
      (node (ref "L2") (pin "1") (pinfunction "1_1") (pintype "passive"))
      (node (ref "U6") (pin "6") (pinfunction "SW_6") (pintype "passive"))
    )
    (net (code "61") (name "Net-(U7-RS)") (class "Default")
      (node (ref "R11") (pin "2") (pinfunction "2_2") (pintype "passive"))
      (node (ref "U7") (pin "8") (pinfunction "RS_8") (pintype "input"))
    )
    (net (code "62") (name "Net-(U10-IN)") (class "Default")
      (node (ref "C26") (pin "1") (pinfunction "1_1") (pintype "passive"))
      (node (ref "L3") (pin "1") (pinfunction "1_1") (pintype "passive"))
      (node (ref "U10") (pin "1") (pinfunction "IN_1") (pintype "power_in"))
    )
    (net (code "63") (name "SUPPLY") (class "Default")
      (node (ref "C16") (pin "1") (pinfunction "1_1") (pintype "passive"))
      (node (ref "C9") (pin "1") (pinfunction "1_1") (pintype "passive"))
      (node (ref "U2") (pin "4") (pinfunction "EN_4") (pintype "passive"))
      (node (ref "U2") (pin "5") (pinfunction "IN_5") (pintype "passive"))
      (node (ref "U6") (pin "4") (pinfunction "EN_4") (pintype "passive"))
      (node (ref "U6") (pin "5") (pinfunction "IN_5") (pintype "passive"))
      (node (ref "X2") (pin "17") (pinfunction "+12_V_17") (pintype "power_in"))
    )
    (net (code "64") (name "unconnected-(U3-ROUT4-Pad10)") (class "Default")
      (node (ref "U3") (pin "10") (pinfunction "ROUT4_10") (pintype "output+no_connect"))
    )
    (net (code "65") (name "unconnected-(U4-ROUT2-Pad14)") (class "Default")
      (node (ref "U4") (pin "14") (pinfunction "ROUT2_14") (pintype "output+no_connect"))
    )
    (net (code "66") (name "unconnected-(U5-PA8-Pad30)") (class "Default")
      (node (ref "U5") (pin "30") (pinfunction "PA8_30") (pintype "bidirectional+no_connect"))
    )
    (net (code "67") (name "unconnected-(U5-PA9-Pad31)") (class "Default")
      (node (ref "U5") (pin "31") (pinfunction "PA9_31") (pintype "bidirectional+no_connect"))
    )
    (net (code "68") (name "unconnected-(U5-PA10-Pad32)") (class "Default")
      (node (ref "U5") (pin "32") (pinfunction "PA10_32") (pintype "bidirectional+no_connect"))
    )
    (net (code "69") (name "unconnected-(U5-PB5-Pad42)") (class "Default")
      (node (ref "U5") (pin "42") (pinfunction "PB5_42") (pintype "bidirectional+no_connect"))
    )
    (net (code "70") (name "unconnected-(U5-PB9-Pad46)") (class "Default")
      (node (ref "U5") (pin "46") (pinfunction "PB9_46") (pintype "bidirectional+no_connect"))
    )
    (net (code "71") (name "unconnected-(U5-PB10-Pad22)") (class "Default")
      (node (ref "U5") (pin "22") (pinfunction "PB10_22") (pintype "bidirectional+no_connect"))
    )
    (net (code "72") (name "unconnected-(U5-PB11-Pad25)") (class "Default")
      (node (ref "U5") (pin "25") (pinfunction "PB11_25") (pintype "bidirectional+no_connect"))
    )
    (net (code "73") (name "unconnected-(U5-PB12-Pad26)") (class "Default")
      (node (ref "U5") (pin "26") (pinfunction "PB12_26") (pintype "bidirectional+no_connect"))
    )
    (net (code "74") (name "unconnected-(U5-PB13-Pad27)") (class "Default")
      (node (ref "U5") (pin "27") (pinfunction "PB13_27") (pintype "bidirectional+no_connect"))
    )
    (net (code "75") (name "unconnected-(U5-PB14-Pad28)") (class "Default")
      (node (ref "U5") (pin "28") (pinfunction "PB14_28") (pintype "bidirectional+no_connect"))
    )
    (net (code "76") (name "unconnected-(U5-PB15-Pad29)") (class "Default")
      (node (ref "U5") (pin "29") (pinfunction "PB15_29") (pintype "bidirectional+no_connect"))
    )
    (net (code "77") (name "unconnected-(U5-PC13-Pad2)") (class "Default")
      (node (ref "U5") (pin "2") (pinfunction "PC13_2") (pintype "bidirectional+no_connect"))
    )
    (net (code "78") (name "unconnected-(U7-VREF-Pad5)") (class "Default")
      (node (ref "U7") (pin "5") (pinfunction "VREF_5") (pintype "output+no_connect"))
    )
    (net (code "79") (name "unconnected-(U8-I{slash}O_4-Pad6)") (class "Default")
      (node (ref "U8") (pin "6") (pinfunction "I/O_4_6") (pintype "passive+no_connect"))
    )
    (net (code "80") (name "unconnected-(U9-I{slash}O_3-Pad4)") (class "Default")
      (node (ref "U9") (pin "4") (pinfunction "I/O_3_4") (pintype "passive+no_connect"))
    )
    (net (code "81") (name "unconnected-(U9-I{slash}O_4-Pad6)") (class "Default")
      (node (ref "U9") (pin "6") (pinfunction "I/O_4_6") (pintype "passive+no_connect"))
    )
  )
)
